# mccd.net
KiCad netlist of a schematic drawn in EAGLE
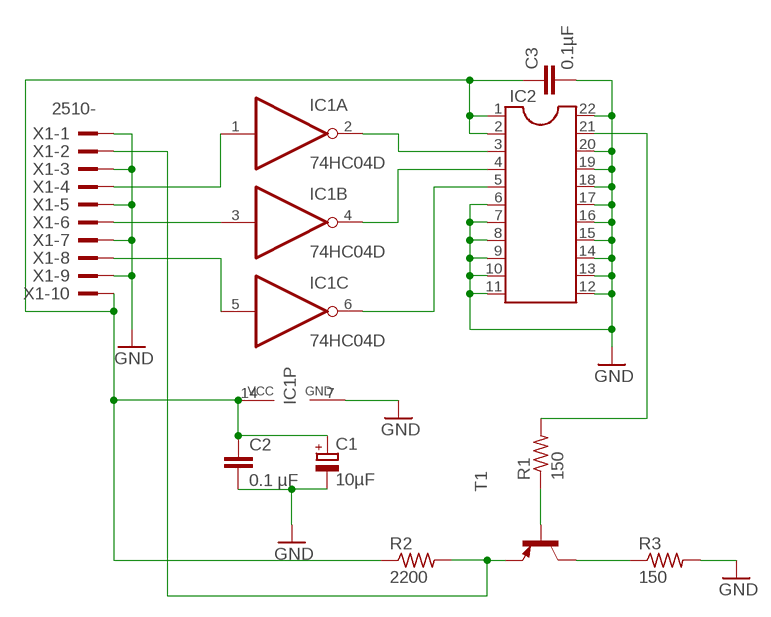
[diagram p0: schematic, sheet 1]

(export (version "E")
  (design (tool "Eeschema 10.0.6"))
  (components
    (comp (ref "C1")
      (value "10µF")
      (footprint "eagle-import:PANASONIC_D")
      (libsource (lib "eagle-import") (part "CPOL-EUD"))
    )
    (comp (ref "C2")
      (value "0.1 µF")
      (footprint "eagle-import:C1206")
      (libsource (lib "eagle-import") (part "C-EUC1206"))
    )
    (comp (ref "C3")
      (value "0.1µF")
      (footprint "eagle-import:C1206")
      (libsource (lib "eagle-import") (part "C-EUC1206"))
    )
    (comp (ref "IC1")
      (value "74HC04D")
      (footprint "eagle-import:SO14")
      (libsource (lib "eagle-import") (part "7404DHC"))
    )
    (comp (ref "IC2")
      (value "DIL22-4")
      (footprint "eagle-import:DIL22-4")
      (libsource (lib "eagle-import") (part "DIL22-4"))
    )
    (comp (ref "R1")
      (value "150")
      (footprint "eagle-import:M1206")
      (libsource (lib "eagle-import") (part "R-US_M1206"))
    )
    (comp (ref "R2")
      (value "2200")
      (footprint "eagle-import:M1206")
      (libsource (lib "eagle-import") (part "R-US_M1206"))
    )
    (comp (ref "R3")
      (value "150")
      (footprint "eagle-import:M1206")
      (libsource (lib "eagle-import") (part "R-US_M1206"))
    )
    (comp (ref "T1")
      (value "-PNP-TO92-BCE")
      (footprint "eagle-import:TO92-BCE")
      (libsource (lib "eagle-import") (part "-PNP-TO92-BCE"))
    )
    (comp (ref "X1")
      (value "2510-")
      (footprint "eagle-import:PAK100_2500-10")
      (fields (field (name "MF") "3M") (field (name "MPN") "2510-6002UB"))
      (libsource (lib "eagle-import") (part "2510-"))
    )
  )
  (nets
    (net (code "1") (name "GND") (class "Default")
      (node (ref "C1") (pin "-") (pinfunction "-_-") (pintype "passive"))
      (node (ref "C2") (pin "2") (pinfunction "2_2") (pintype "passive"))
      (node (ref "C3") (pin "2") (pinfunction "2_2") (pintype "passive"))
      (node (ref "IC1") (pin "7") (pinfunction "GND_7") (pintype "power_in"))
      (node (ref "IC2") (pin "10") (pinfunction "10_10") (pintype "passive"))
      (node (ref "IC2") (pin "11") (pinfunction "11_11") (pintype "passive"))
      (node (ref "IC2") (pin "12") (pinfunction "12_12") (pintype "passive"))
      (node (ref "IC2") (pin "13") (pinfunction "13_13") (pintype "passive"))
      (node (ref "IC2") (pin "14") (pinfunction "14_14") (pintype "passive"))
      (node (ref "IC2") (pin "15") (pinfunction "15_15") (pintype "passive"))
      (node (ref "IC2") (pin "16") (pinfunction "16_16") (pintype "passive"))
      (node (ref "IC2") (pin "17") (pinfunction "17_17") (pintype "passive"))
      (node (ref "IC2") (pin "18") (pinfunction "18_18") (pintype "passive"))
      (node (ref "IC2") (pin "19") (pinfunction "19_19") (pintype "passive"))
      (node (ref "IC2") (pin "20") (pinfunction "20_20") (pintype "passive"))
      (node (ref "IC2") (pin "22") (pinfunction "22_22") (pintype "passive"))
      (node (ref "IC2") (pin "6") (pinfunction "6_6") (pintype "passive"))
      (node (ref "IC2") (pin "7") (pinfunction "7_7") (pintype "passive"))
      (node (ref "IC2") (pin "8") (pinfunction "8_8") (pintype "passive"))
      (node (ref "IC2") (pin "9") (pinfunction "9_9") (pintype "passive"))
      (node (ref "R3") (pin "2") (pinfunction "2_2") (pintype "passive"))
      (node (ref "X1") (pin "1") (pinfunction "KL_1") (pintype "passive"))
      (node (ref "X1") (pin "3") (pinfunction "KL_3") (pintype "passive"))
      (node (ref "X1") (pin "5") (pinfunction "KL_5") (pintype "passive"))
      (node (ref "X1") (pin "7") (pinfunction "KL_7") (pintype "passive"))
      (node (ref "X1") (pin "9") (pinfunction "KL_9") (pintype "passive"))
    )
    (net (code "2") (name "Net-(IC1A-I)") (class "Default")
      (node (ref "IC1") (pin "1") (pinfunction "I_1") (pintype "input"))
      (node (ref "X1") (pin "4") (pinfunction "KL_4") (pintype "passive"))
    )
    (net (code "3") (name "Net-(IC1A-O)") (class "Default")
      (node (ref "IC1") (pin "2") (pinfunction "O_2") (pintype "output"))
      (node (ref "IC2") (pin "3") (pinfunction "3_3") (pintype "passive"))
    )
    (net (code "4") (name "Net-(IC1B-I)") (class "Default")
      (node (ref "IC1") (pin "3") (pinfunction "I_3") (pintype "input"))
      (node (ref "X1") (pin "6") (pinfunction "KL_6") (pintype "passive"))
    )
    (net (code "5") (name "Net-(IC1B-O)") (class "Default")
      (node (ref "IC1") (pin "4") (pinfunction "O_4") (pintype "output"))
      (node (ref "IC2") (pin "4") (pinfunction "4_4") (pintype "passive"))
    )
    (net (code "6") (name "Net-(IC1C-I)") (class "Default")
      (node (ref "IC1") (pin "5") (pinfunction "I_5") (pintype "input"))
      (node (ref "X1") (pin "8") (pinfunction "KL_8") (pintype "passive"))
    )
    (net (code "7") (name "Net-(IC1C-O)") (class "Default")
      (node (ref "IC1") (pin "6") (pinfunction "O_6") (pintype "output"))
      (node (ref "IC2") (pin "5") (pinfunction "5_5") (pintype "passive"))
    )
    (net (code "8") (name "Net-(IC1G-VCC)") (class "Default")
      (node (ref "C1") (pin "+") (pinfunction "+_+") (pintype "passive"))
      (node (ref "C2") (pin "1") (pinfunction "1_1") (pintype "passive"))
      (node (ref "C3") (pin "1") (pinfunction "1_1") (pintype "passive"))
      (node (ref "IC1") (pin "14") (pinfunction "VCC_14") (pintype "power_in"))
      (node (ref "IC2") (pin "1") (pinfunction "1_1") (pintype "passive"))
      (node (ref "IC2") (pin "2") (pinfunction "2_2") (pintype "passive"))
      (node (ref "R2") (pin "1") (pinfunction "1_1") (pintype "passive"))
      (node (ref "X1") (pin "10") (pinfunction "KL_10") (pintype "passive"))
    )
    (net (code "9") (name "Net-(IC2-Pad21)") (class "Default")
      (node (ref "IC2") (pin "21") (pinfunction "21_21") (pintype "passive"))
      (node (ref "R1") (pin "2") (pinfunction "2_2") (pintype "passive"))
    )
    (net (code "10") (name "Net-(R1-Pad1)") (class "Default")
      (node (ref "R1") (pin "1") (pinfunction "1_1") (pintype "passive"))
      (node (ref "T1") (pin "B") (pinfunction "B_B") (pintype "passive"))
    )
    (net (code "11") (name "Net-(R3-Pad1)") (class "Default")
      (node (ref "R3") (pin "1") (pinfunction "1_1") (pintype "passive"))
      (node (ref "T1") (pin "C") (pinfunction "C_C") (pintype "passive"))
    )
    (net (code "12") (name "Net-(X1C-KL)") (class "Default")
      (node (ref "R2") (pin "2") (pinfunction "2_2") (pintype "passive"))
      (node (ref "T1") (pin "E") (pinfunction "E_E") (pintype "passive"))
      (node (ref "X1") (pin "2") (pinfunction "KL_2") (pintype "passive"))
    )
  )
)
